# power.net
KiCad netlist of a schematic drawn in Altium Designer
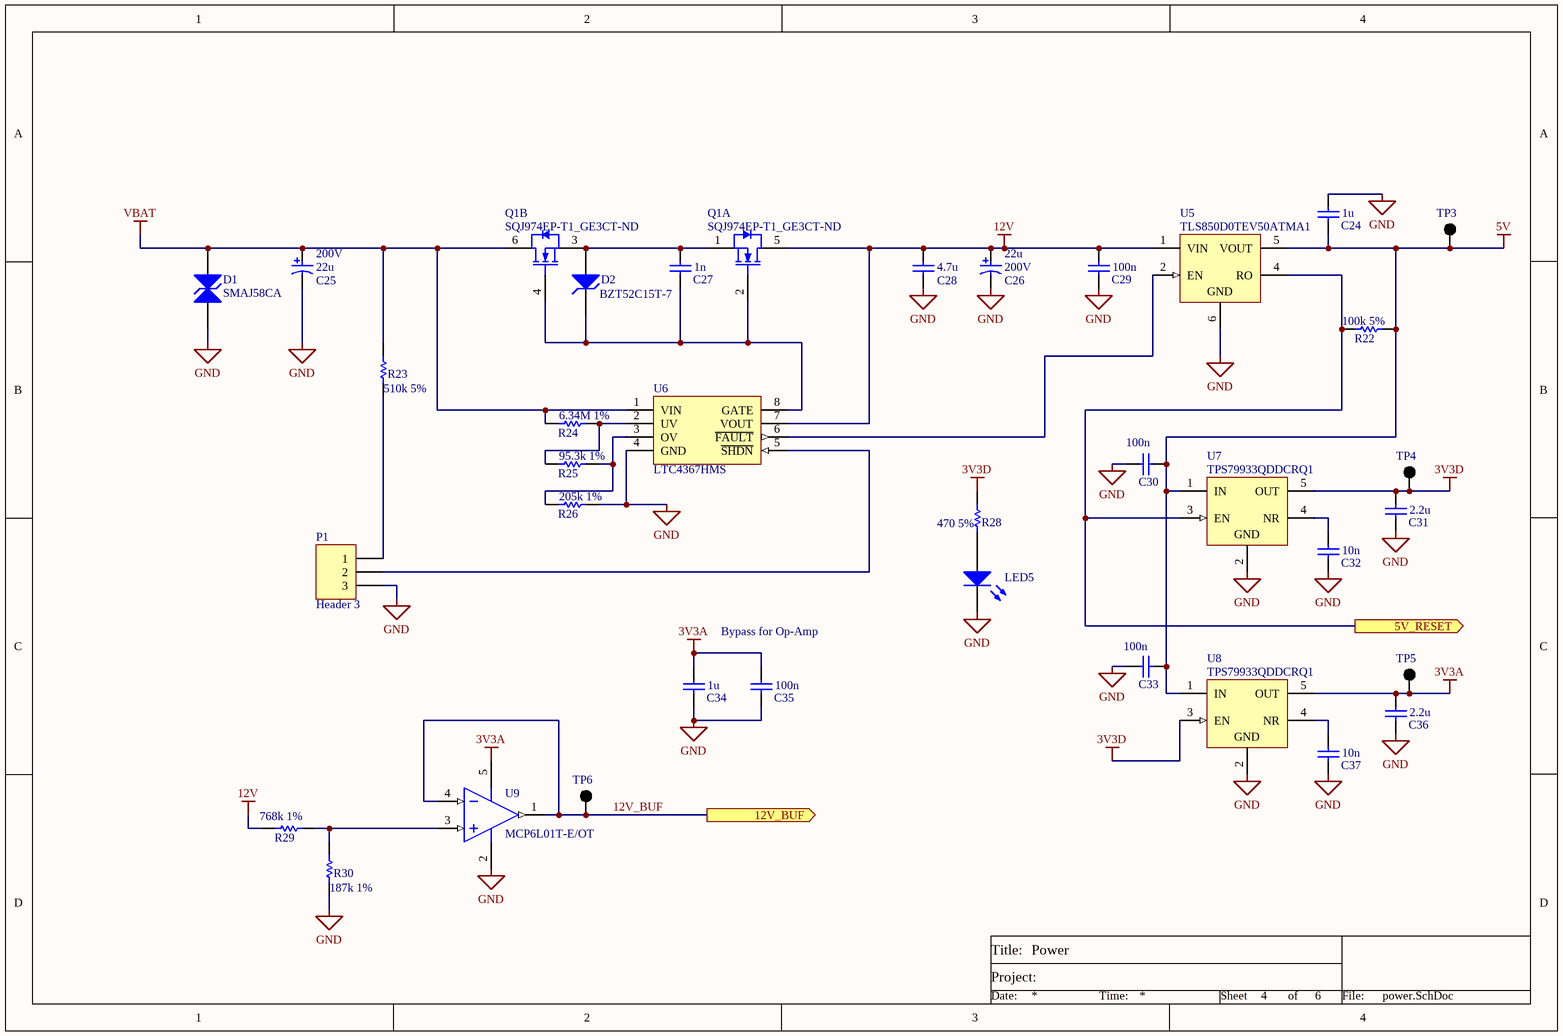
[diagram p0: power.SchDoc]

(export (version "E")
  (design (tool "Eeschema 10.0.6"))
  (components
    (comp (ref "C24")
      (value "1u")
      (footprint "0805")
      (description "Generic 0805 Capacitor")
      (libsource (lib "symbol_library") (part "C_0805"))
    )
    (comp (ref "C25")
      (value "22u")
      (footprint "NIC-UUX2A470MNL1GS_M")
      (description "Generic PCAP_10x10 Can Aluminum Electrolytic Capacitor")
      (fields (field (name "VOLTAGE") "200V") (field (name "Comment") "Generic Electrolytic Capacitor"))
      (libsource (lib "symbol_library") (part "C_can"))
    )
    (comp (ref "C26")
      (value "22u")
      (footprint "NIC-UUX2A470MNL1GS_M")
      (description "Generic PCAP_10x10 Can Aluminum Electrolytic Capacitor")
      (fields (field (name "VOLTAGE") "200V") (field (name "Comment") "Generic Electrolytic Capacitor"))
      (libsource (lib "symbol_library") (part "C_can"))
    )
    (comp (ref "C27")
      (value "1n")
      (footprint "0805")
      (description "Generic 0805 Capacitor")
      (libsource (lib "symbol_library") (part "C_0805"))
    )
    (comp (ref "C28")
      (value "4.7u")
      (footprint "0805")
      (description "Generic 0805 Capacitor")
      (libsource (lib "symbol_library") (part "C_0805"))
    )
    (comp (ref "C29")
      (value "100n")
      (footprint "0805")
      (description "Generic 0805 Capacitor")
      (libsource (lib "symbol_library") (part "C_0805"))
    )
    (comp (ref "C30")
      (value "100n")
      (footprint "0805")
      (description "Generic 0805 Capacitor")
      (libsource (lib "symbol_library") (part "C_0805"))
    )
    (comp (ref "C31")
      (value "2.2u")
      (footprint "0805")
      (description "Generic 0805 Capacitor")
      (libsource (lib "symbol_library") (part "C_0805"))
    )
    (comp (ref "C32")
      (value "10n")
      (footprint "0805")
      (description "Generic 0805 Capacitor")
      (libsource (lib "symbol_library") (part "C_0805"))
    )
    (comp (ref "C33")
      (value "100n")
      (footprint "0805")
      (description "Generic 0805 Capacitor")
      (libsource (lib "symbol_library") (part "C_0805"))
    )
    (comp (ref "C34")
      (value "1u")
      (footprint "0805")
      (description "Generic 0805 Capacitor")
      (libsource (lib "symbol_library") (part "C_0805"))
    )
    (comp (ref "C35")
      (value "100n")
      (footprint "0805")
      (description "Generic 0805 Capacitor")
      (libsource (lib "symbol_library") (part "C_0805"))
    )
    (comp (ref "C36")
      (value "2.2u")
      (footprint "0805")
      (description "Generic 0805 Capacitor")
      (libsource (lib "symbol_library") (part "C_0805"))
    )
    (comp (ref "C37")
      (value "10n")
      (footprint "0805")
      (description "Generic 0805 Capacitor")
      (libsource (lib "symbol_library") (part "C_0805"))
    )
    (comp (ref "D1")
      (value "SMAJ58CA")
      (footprint "VISH-DO-214AC-2_M")
      (fields
        (field (name "MANUFACTURER") "Vishay Semiconductor")
        (field (name "PARTNUMBER") "SMAJ58CA-E3/5A")
      )
      (libsource (lib "symbol_library") (part "SMAJ58CA"))
    )
    (comp (ref "D2")
      (value "BZT52C15T-7")
      (footprint "DIOD-SOD123-2_V")
      (description "Zener Diode 15V 300mW ±6% Surface Mount SOD-523")
      (fields (field (name "MANUFACTURER") "Diodes Inc") (field (name "PARTNUMBER") "BZT52C16-7-F"))
      (libsource (lib "symbol_library") (part "BZT52C15T"))
    )
    (comp (ref "LED5")
      (value "150080SS75000")
      (footprint "0805_A")
      (description "SMD mono-color Chip LED, WL-SMCW, Super Red")
      (fields (field (name "MANUFACTURER") "Wuerth Elektronik"))
      (libsource (lib "symbol_library") (part "LED_0805"))
    )
    (comp (ref "P1")
      (value "Header 3")
      (footprint "HDR1X3")
      (description "Header, 3-Pin")
      (fields (field (name "PUBLISHER") "Altium Limited"))
      (libsource (lib "Miscellaneous Connectors") (part "Header 3"))
    )
    (comp (ref "Q1")
      (value "SQJ974EP-T1_GE3CT-ND")
      (footprint "VISH-POWERPAKSO-8_A_V")
      (description "Mosfet Array 2 N-Channel (Dual) 100V 30A (Tc) 48W Surface Mount PowerPAK® SO-8 Dual")
      (fields (field (name "MANUFACTURER") "Vishay"))
      (libsource (lib "symbol_library") (part "SQJ974EP"))
    )
    (comp (ref "R22")
      (value "100k 5%")
      (footprint "0603")
      (description "Generic 0603 Resistor")
      (libsource (lib "symbol_library") (part "R_0603"))
    )
    (comp (ref "R23")
      (value "510k 5%")
      (footprint "0603")
      (description "Generic 0603 Resistor")
      (libsource (lib "symbol_library") (part "R_0603"))
    )
    (comp (ref "R24")
      (value "6.34M 1%")
      (footprint "0603")
      (description "Generic 0603 Resistor")
      (libsource (lib "symbol_library") (part "R_0603"))
    )
    (comp (ref "R25")
      (value "95.3k 1%")
      (footprint "0603")
      (description "Generic 0603 Resistor")
      (libsource (lib "symbol_library") (part "R_0603"))
    )
    (comp (ref "R26")
      (value "205k 1%")
      (footprint "0603")
      (description "Generic 0603 Resistor")
      (libsource (lib "symbol_library") (part "R_0603"))
    )
    (comp (ref "R28")
      (value "470 5%")
      (footprint "0603")
      (description "Generic 0603 Resistor")
      (libsource (lib "symbol_library") (part "R_0603"))
    )
    (comp (ref "R29")
      (value "768k 1%")
      (footprint "0603")
      (description "Generic 0603 Resistor")
      (libsource (lib "symbol_library") (part "R_0603"))
    )
    (comp (ref "R30")
      (value "187k 1%")
      (footprint "0603")
      (description "Generic 0603 Resistor")
      (libsource (lib "symbol_library") (part "R_0603"))
    )
    (comp (ref "TP3")
      (value "5001")
      (footprint "KSTN-5001")
      (description "Test Point, Black, 1-Pin THD, RoHS, Bulk")
      (fields (field (name "MANUFACTURER") "Keystone"))
      (libsource (lib "symbol_library") (part "TP5001"))
    )
    (comp (ref "TP4")
      (value "5001")
      (footprint "KSTN-5001")
      (description "Test Point, Black, 1-Pin THD, RoHS, Bulk")
      (fields (field (name "MANUFACTURER") "Keystone"))
      (libsource (lib "symbol_library") (part "TP5001"))
    )
    (comp (ref "TP5")
      (value "5001")
      (footprint "KSTN-5001")
      (description "Test Point, Black, 1-Pin THD, RoHS, Bulk")
      (fields (field (name "MANUFACTURER") "Keystone"))
      (libsource (lib "symbol_library") (part "TP5001"))
    )
    (comp (ref "TP6")
      (value "5001")
      (footprint "KSTN-5001")
      (description "Test Point, Black, 1-Pin THD, RoHS, Bulk")
      (fields (field (name "MANUFACTURER") "Keystone"))
      (libsource (lib "symbol_library") (part "TP5001"))
    )
    (comp (ref "U5")
      (value "TLS850D0TEV50ATMA1")
      (footprint "KVU0005A_M")
      (description "Linear Voltage Regulator IC  1 Output  500mA PG-TO252-5")
      (fields
        (field (name "PARTNUMBER") "TPS7A6150QKVURQ1")
        (field (name "MANUFACTURER") "Texas Instruments")
      )
      (libsource (lib "symbol_library") (part "TLS850D0TE"))
    )
    (comp (ref "U6")
      (value "LTC4367HMS")
      (footprint "MSOP8_M")
      (description "100V Overvoltage, Undervoltage and Reverse Supply Protection Controller")
      (libsource (lib "symbol_library") (part "LTC4367"))
    )
    (comp (ref "U7")
      (value "TPS79933QDDCRQ1")
      (footprint "DDC0005A_M")
      (fields (field (name "MANUFACTURER") "Texas Instruments"))
      (libsource (lib "symbol_library") (part "TPS79933"))
    )
    (comp (ref "U8")
      (value "TPS79933QDDCRQ1")
      (footprint "DDC0005A_M")
      (fields (field (name "MANUFACTURER") "Texas Instruments"))
      (libsource (lib "symbol_library") (part "TPS79933"))
    )
    (comp (ref "U9")
      (value "MCP6L01T-E/OT")
      (footprint "DDC0005A_M")
      (description "1 MHz, 85 uA Op Amp, 5-Pin SOT-23, Extended Temperature Range")
      (libsource (lib "symbol_library") (part "MCP6L01"))
    )
  )
  (nets
    (net (code "1") (name "/5V_RESET") (class "Default")
      (node (ref "R22") (pin "1") (pinfunction "1_1") (pintype "passive"))
      (node (ref "U5") (pin "4") (pinfunction "RO_4") (pintype "open_collector"))
      (node (ref "U7") (pin "3") (pinfunction "EN_3") (pintype "input"))
    )
    (net (code "2") (name "/12V_BUF") (class "Default")
      (node (ref "TP6") (pin "1") (pintype "passive"))
      (node (ref "U9") (pin "1") (pinfunction "VOUT_1") (pintype "output"))
      (node (ref "U9") (pin "4") (pinfunction "VIN-_4") (pintype "input"))
    )
    (net (code "3") (name "3V3A") (class "Default")
      (node (ref "C34") (pin "2") (pinfunction "2_2") (pintype "passive"))
      (node (ref "C35") (pin "2") (pinfunction "2_2") (pintype "passive"))
      (node (ref "C36") (pin "2") (pinfunction "2_2") (pintype "passive"))
      (node (ref "TP5") (pin "1") (pintype "passive"))
      (node (ref "U8") (pin "5") (pinfunction "OUT_5") (pintype "power_in"))
      (node (ref "U9") (pin "5") (pinfunction "VDD_5") (pintype "power_in"))
    )
    (net (code "4") (name "3V3D") (class "Default")
      (node (ref "C31") (pin "2") (pinfunction "2_2") (pintype "passive"))
      (node (ref "R28") (pin "2") (pinfunction "2_2") (pintype "passive"))
      (node (ref "TP4") (pin "1") (pintype "passive"))
      (node (ref "U7") (pin "5") (pinfunction "OUT_5") (pintype "power_in"))
      (node (ref "U8") (pin "3") (pinfunction "EN_3") (pintype "input"))
    )
    (net (code "5") (name "5V") (class "Default")
      (node (ref "C24") (pin "1") (pinfunction "1_1") (pintype "passive"))
      (node (ref "C30") (pin "2") (pinfunction "2_2") (pintype "passive"))
      (node (ref "C33") (pin "1") (pinfunction "1_1") (pintype "passive"))
      (node (ref "R22") (pin "2") (pinfunction "2_2") (pintype "passive"))
      (node (ref "TP3") (pin "1") (pintype "passive"))
      (node (ref "U5") (pin "5") (pinfunction "VOUT_5") (pintype "power_in"))
      (node (ref "U7") (pin "1") (pinfunction "IN_1") (pintype "power_in"))
      (node (ref "U8") (pin "1") (pinfunction "IN_1") (pintype "power_in"))
    )
    (net (code "6") (name "12V") (class "Default")
      (node (ref "C26") (pin "1") (pinfunction "1_1") (pintype "passive"))
      (node (ref "C28") (pin "2") (pinfunction "2_2") (pintype "passive"))
      (node (ref "C29") (pin "2") (pinfunction "2_2") (pintype "passive"))
      (node (ref "Q1") (pin "5") (pinfunction "G2_5") (pintype "passive"))
      (node (ref "R29") (pin "1") (pinfunction "1_1") (pintype "passive"))
      (node (ref "U5") (pin "1") (pinfunction "VIN_1") (pintype "power_in"))
      (node (ref "U6") (pin "7") (pinfunction "VOUT_7") (pintype "passive"))
    )
    (net (code "7") (name "GND") (class "Default")
      (node (ref "C24") (pin "2") (pinfunction "2_2") (pintype "passive"))
      (node (ref "C25") (pin "2") (pinfunction "2_2") (pintype "passive"))
      (node (ref "C26") (pin "2") (pinfunction "2_2") (pintype "passive"))
      (node (ref "C28") (pin "1") (pinfunction "1_1") (pintype "passive"))
      (node (ref "C29") (pin "1") (pinfunction "1_1") (pintype "passive"))
      (node (ref "C30") (pin "1") (pinfunction "1_1") (pintype "passive"))
      (node (ref "C31") (pin "1") (pinfunction "1_1") (pintype "passive"))
      (node (ref "C32") (pin "1") (pinfunction "1_1") (pintype "passive"))
      (node (ref "C33") (pin "2") (pinfunction "2_2") (pintype "passive"))
      (node (ref "C34") (pin "1") (pinfunction "1_1") (pintype "passive"))
      (node (ref "C35") (pin "1") (pinfunction "1_1") (pintype "passive"))
      (node (ref "C36") (pin "1") (pinfunction "1_1") (pintype "passive"))
      (node (ref "C37") (pin "1") (pinfunction "1_1") (pintype "passive"))
      (node (ref "D1") (pin "1") (pinfunction "A1_1") (pintype "passive"))
      (node (ref "LED5") (pin "1") (pinfunction "K_1") (pintype "passive"))
      (node (ref "P1") (pin "3") (pinfunction "3_3") (pintype "passive"))
      (node (ref "R26") (pin "2") (pinfunction "2_2") (pintype "passive"))
      (node (ref "R30") (pin "1") (pinfunction "1_1") (pintype "passive"))
      (node (ref "U5") (pin "6") (pinfunction "GND_6") (pintype "power_in"))
      (node (ref "U6") (pin "4") (pinfunction "GND_4") (pintype "power_in"))
      (node (ref "U7") (pin "2") (pinfunction "GND_2") (pintype "power_in"))
      (node (ref "U8") (pin "2") (pinfunction "GND_2") (pintype "power_in"))
      (node (ref "U9") (pin "2") (pinfunction "VSS_2") (pintype "power_in"))
    )
    (net (code "8") (name "Net-(D2-A)") (class "Default")
      (node (ref "C27") (pin "2") (pinfunction "2_2") (pintype "passive"))
      (node (ref "D2") (pin "1") (pinfunction "A_1") (pintype "passive"))
      (node (ref "Q1") (pin "1") (pinfunction "S2_1") (pintype "passive"))
      (node (ref "Q1") (pin "3") (pinfunction "S2_3") (pintype "passive"))
    )
    (net (code "9") (name "Net-(D2-K)") (class "Default")
      (node (ref "C27") (pin "1") (pinfunction "1_1") (pintype "passive"))
      (node (ref "D2") (pin "2") (pinfunction "K_2") (pintype "passive"))
      (node (ref "Q1") (pin "2") (pinfunction "G2_2") (pintype "passive"))
      (node (ref "Q1") (pin "4") (pinfunction "G2_4") (pintype "passive"))
      (node (ref "U6") (pin "8") (pinfunction "GATE_8") (pintype "passive"))
    )
    (net (code "10") (name "Net-(LED5-A)") (class "Default")
      (node (ref "LED5") (pin "2") (pinfunction "A_2") (pintype "passive"))
      (node (ref "R28") (pin "1") (pinfunction "1_1") (pintype "passive"))
    )
    (net (code "11") (name "Net-(P1-Pad1)") (class "Default")
      (node (ref "P1") (pin "1") (pinfunction "1_1") (pintype "passive"))
      (node (ref "R23") (pin "1") (pinfunction "1_1") (pintype "passive"))
    )
    (net (code "12") (name "Net-(U5-EN)") (class "Default")
      (node (ref "U5") (pin "2") (pinfunction "EN_2") (pintype "input"))
      (node (ref "U6") (pin "6") (pinfunction "~{FAULT}_6") (pintype "output"))
    )
    (net (code "13") (name "Net-(U6-OV)") (class "Default")
      (node (ref "R25") (pin "2") (pinfunction "2_2") (pintype "passive"))
      (node (ref "R26") (pin "1") (pinfunction "1_1") (pintype "passive"))
      (node (ref "U6") (pin "3") (pinfunction "OV_3") (pintype "passive"))
    )
    (net (code "14") (name "Net-(U6-UV)") (class "Default")
      (node (ref "R24") (pin "2") (pinfunction "2_2") (pintype "passive"))
      (node (ref "R25") (pin "1") (pinfunction "1_1") (pintype "passive"))
      (node (ref "U6") (pin "2") (pinfunction "UV_2") (pintype "passive"))
    )
    (net (code "15") (name "Net-(U6-~{SHDN})") (class "Default")
      (node (ref "P1") (pin "2") (pinfunction "2_2") (pintype "passive"))
      (node (ref "U6") (pin "5") (pinfunction "~{SHDN}_5") (pintype "input"))
    )
    (net (code "16") (name "Net-(U7-NR)") (class "Default")
      (node (ref "C32") (pin "2") (pinfunction "2_2") (pintype "passive"))
      (node (ref "U7") (pin "4") (pinfunction "NR_4") (pintype "passive"))
    )
    (net (code "17") (name "Net-(U8-NR)") (class "Default")
      (node (ref "C37") (pin "2") (pinfunction "2_2") (pintype "passive"))
      (node (ref "U8") (pin "4") (pinfunction "NR_4") (pintype "passive"))
    )
    (net (code "18") (name "Net-(U9-VIN+)") (class "Default")
      (node (ref "R29") (pin "2") (pinfunction "2_2") (pintype "passive"))
      (node (ref "R30") (pin "2") (pinfunction "2_2") (pintype "passive"))
      (node (ref "U9") (pin "3") (pinfunction "VIN+_3") (pintype "input"))
    )
    (net (code "19") (name "VBAT") (class "Default")
      (node (ref "C25") (pin "1") (pinfunction "1_1") (pintype "passive"))
      (node (ref "D1") (pin "2") (pinfunction "A2_2") (pintype "passive"))
      (node (ref "Q1") (pin "6") (pinfunction "G2_6") (pintype "passive"))
      (node (ref "R23") (pin "2") (pinfunction "2_2") (pintype "passive"))
      (node (ref "R24") (pin "1") (pinfunction "1_1") (pintype "passive"))
      (node (ref "U6") (pin "1") (pinfunction "VIN_1") (pintype "power_in"))
    )
  )
)
